# car.net
KiCad netlist of a schematic drawn in EAGLE
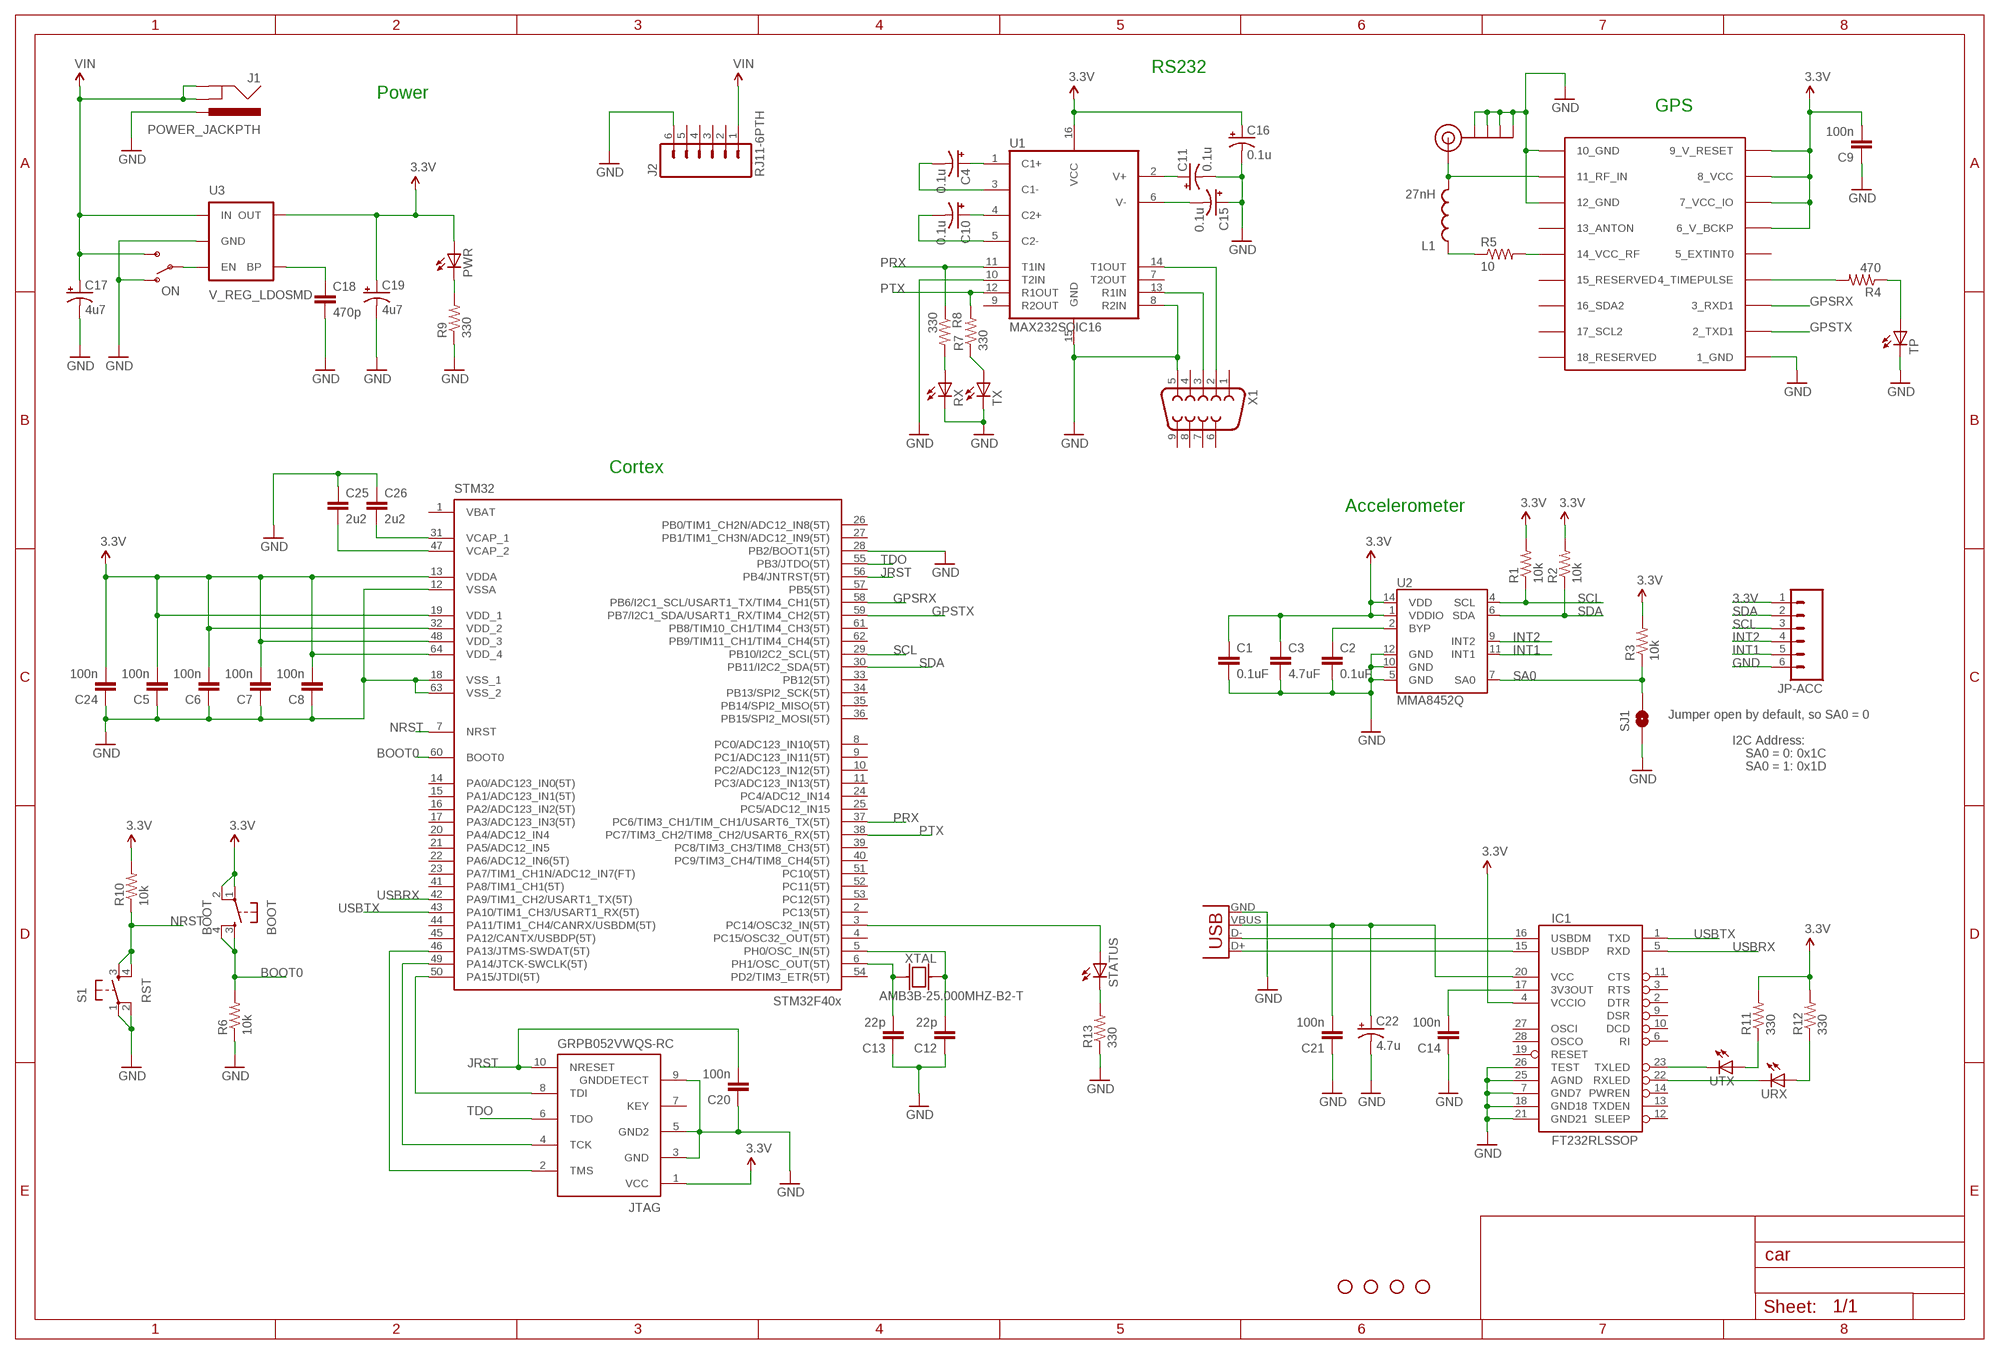
[diagram p0: schematic, sheet 1]

(export (version "E")
  (design (tool "Eeschema 10.0.6"))
  (components
    (comp (ref "BOOT")
      (value "BOOT")
      (footprint "eagle-import:TACTILE_SWITCH_SMD")
      (libsource (lib "eagle-import") (part "TAC_SWITCHSMD"))
    )
    (comp (ref "C1")
      (value "0.1uF")
      (footprint "eagle-import:0603-CAP")
      (libsource (lib "eagle-import") (part "CAP0603-CAP"))
    )
    (comp (ref "C2")
      (value "0.1uF")
      (footprint "eagle-import:0603-CAP")
      (libsource (lib "eagle-import") (part "CAP0603-CAP"))
    )
    (comp (ref "C3")
      (value "4.7uF")
      (footprint "eagle-import:0603-CAP")
      (libsource (lib "eagle-import") (part "CAP0603-CAP"))
    )
    (comp (ref "C4")
      (value "0.1u")
      (footprint "eagle-import:EIA3216")
      (libsource (lib "eagle-import") (part "CAP_POL1206"))
    )
    (comp (ref "C5")
      (value "100n")
      (footprint "eagle-import:0603-CAP")
      (libsource (lib "eagle-import") (part "SparkFun-Passives_CAP0603-CAP"))
    )
    (comp (ref "C6")
      (value "100n")
      (footprint "eagle-import:0603-CAP")
      (libsource (lib "eagle-import") (part "SparkFun-Passives_CAP0603-CAP"))
    )
    (comp (ref "C7")
      (value "100n")
      (footprint "eagle-import:0603-CAP")
      (libsource (lib "eagle-import") (part "SparkFun-Passives_CAP0603-CAP"))
    )
    (comp (ref "C8")
      (value "100n")
      (footprint "eagle-import:0603-CAP")
      (libsource (lib "eagle-import") (part "SparkFun-Passives_CAP0603-CAP"))
    )
    (comp (ref "C9")
      (value "100n")
      (footprint "eagle-import:0603-CAP")
      (libsource (lib "eagle-import") (part "SparkFun-Passives_CAP0603-CAP"))
    )
    (comp (ref "C10")
      (value "0.1u")
      (footprint "eagle-import:EIA3216")
      (libsource (lib "eagle-import") (part "CAP_POL1206"))
    )
    (comp (ref "C11")
      (value "0.1u")
      (footprint "eagle-import:EIA3216")
      (libsource (lib "eagle-import") (part "CAP_POL1206"))
    )
    (comp (ref "C12")
      (value "22p")
      (footprint "eagle-import:0603-CAP")
      (libsource (lib "eagle-import") (part "SparkFun-Passives_CAP0603-CAP"))
    )
    (comp (ref "C13")
      (value "22p")
      (footprint "eagle-import:0603-CAP")
      (libsource (lib "eagle-import") (part "SparkFun-Passives_CAP0603-CAP"))
    )
    (comp (ref "C14")
      (value "100n")
      (footprint "eagle-import:0603-CAP")
      (libsource (lib "eagle-import") (part "SparkFun-Passives_CAP0603-CAP"))
    )
    (comp (ref "C15")
      (value "0.1u")
      (footprint "eagle-import:EIA3216")
      (libsource (lib "eagle-import") (part "CAP_POL1206"))
    )
    (comp (ref "C16")
      (value "0.1u")
      (footprint "eagle-import:EIA3216")
      (libsource (lib "eagle-import") (part "CAP_POL1206"))
    )
    (comp (ref "C17")
      (value "4u7")
      (footprint "eagle-import:EIA3216")
      (libsource (lib "eagle-import") (part "CAP_POL1206"))
    )
    (comp (ref "C18")
      (value "470p")
      (footprint "eagle-import:0603-CAP")
      (libsource (lib "eagle-import") (part "SparkFun-Passives_CAP0603-CAP"))
    )
    (comp (ref "C19")
      (value "4u7")
      (footprint "eagle-import:EIA3216")
      (libsource (lib "eagle-import") (part "CAP_POL1206"))
    )
    (comp (ref "C20")
      (value "100n")
      (footprint "eagle-import:0603-CAP")
      (libsource (lib "eagle-import") (part "SparkFun-Passives_CAP0603-CAP"))
    )
    (comp (ref "C21")
      (value "100n")
      (footprint "eagle-import:0603-CAP")
      (libsource (lib "eagle-import") (part "SparkFun-Passives_CAP0603-CAP"))
    )
    (comp (ref "C22")
      (value "4.7u")
      (footprint "eagle-import:EIA3216")
      (libsource (lib "eagle-import") (part "CAP_POL1206"))
    )
    (comp (ref "C24")
      (value "100n")
      (footprint "eagle-import:0603-CAP")
      (libsource (lib "eagle-import") (part "SparkFun-Passives_CAP0603-CAP"))
    )
    (comp (ref "C25")
      (value "2u2")
      (footprint "eagle-import:0603-CAP")
      (libsource (lib "eagle-import") (part "SparkFun-Passives_CAP0603-CAP"))
    )
    (comp (ref "C26")
      (value "2u2")
      (footprint "eagle-import:0603-CAP")
      (libsource (lib "eagle-import") (part "SparkFun-Passives_CAP0603-CAP"))
    )
    (comp (ref "IC1")
      (value "FT232RLSSOP")
      (footprint "eagle-import:SSOP28DB")
      (libsource (lib "eagle-import") (part "FT232RLSSOP"))
    )
    (comp (ref "J$1")
      (value "SMA_EDGE")
      (footprint "eagle-import:SMA-EDGE")
      (libsource (lib "eagle-import") (part "SMA_EDGE"))
    )
    (comp (ref "J1")
      (value "POWER_JACKPTH")
      (footprint "eagle-import:POWER_JACK_PTH")
      (libsource (lib "eagle-import") (part "POWER_JACKPTH"))
    )
    (comp (ref "J2")
      (value "RJ11-6PTH")
      (footprint "eagle-import:RJ11-6")
      (libsource (lib "eagle-import") (part "RJ11-6PTH"))
    )
    (comp (ref "JP-ACC")
      (value "M06SIP")
      (footprint "eagle-import:1X06")
      (libsource (lib "eagle-import") (part "M06SIP"))
    )
    (comp (ref "JP1")
      (value "STAND-OFF")
      (footprint "eagle-import:STAND-OFF")
      (libsource (lib "eagle-import") (part "STAND-OFF"))
    )
    (comp (ref "JP2")
      (value "STAND-OFF")
      (footprint "eagle-import:STAND-OFF")
      (libsource (lib "eagle-import") (part "STAND-OFF"))
    )
    (comp (ref "JP3")
      (value "STAND-OFF")
      (footprint "eagle-import:STAND-OFF")
      (libsource (lib "eagle-import") (part "STAND-OFF"))
    )
    (comp (ref "JP4")
      (value "STAND-OFF")
      (footprint "eagle-import:STAND-OFF")
      (libsource (lib "eagle-import") (part "STAND-OFF"))
    )
    (comp (ref "JTAG")
      (value "GRPB052VWQS-RC")
      (footprint "eagle-import:DEBUG")
      (libsource (lib "eagle-import") (part "GRPB052VWQS-RC"))
    )
    (comp (ref "L1")
      (value "27nH")
      (footprint "eagle-import:0603")
      (libsource (lib "eagle-import") (part "INDUCTOR0603"))
    )
    (comp (ref "ON")
      (value "SWITCH-SPDTPTH")
      (footprint "eagle-import:SWITCH-SPDT")
      (libsource (lib "eagle-import") (part "SWITCH-SPDTPTH"))
    )
    (comp (ref "PWR")
      (value "LED0603")
      (footprint "eagle-import:LED-0603")
      (libsource (lib "eagle-import") (part "LED0603"))
    )
    (comp (ref "R1")
      (value "10k")
      (footprint "eagle-import:0603-RES")
      (libsource (lib "eagle-import") (part "RESISTOR0603-RES"))
    )
    (comp (ref "R2")
      (value "10k")
      (footprint "eagle-import:0603-RES")
      (libsource (lib "eagle-import") (part "RESISTOR0603-RES"))
    )
    (comp (ref "R3")
      (value "10k")
      (footprint "eagle-import:0603-RES")
      (libsource (lib "eagle-import") (part "RESISTOR0603-RES"))
    )
    (comp (ref "R4")
      (value "470")
      (footprint "eagle-import:0603-RES")
      (libsource (lib "eagle-import") (part "SparkFun-Passives_RESISTOR0603-RES"))
    )
    (comp (ref "R5")
      (value "10")
      (footprint "eagle-import:0603-RES")
      (libsource (lib "eagle-import") (part "SparkFun-Passives_RESISTOR0603-RES"))
    )
    (comp (ref "R6")
      (value "10k")
      (footprint "eagle-import:0603-RES")
      (libsource (lib "eagle-import") (part "SparkFun-Passives_RESISTOR0603-RES"))
    )
    (comp (ref "R7")
      (value "330")
      (footprint "eagle-import:0603-RES")
      (libsource (lib "eagle-import") (part "SparkFun-Passives_RESISTOR0603-RES"))
    )
    (comp (ref "R8")
      (value "330")
      (footprint "eagle-import:0603-RES")
      (libsource (lib "eagle-import") (part "SparkFun-Passives_RESISTOR0603-RES"))
    )
    (comp (ref "R9")
      (value "330")
      (footprint "eagle-import:0603-RES")
      (libsource (lib "eagle-import") (part "SparkFun-Passives_RESISTOR0603-RES"))
    )
    (comp (ref "R10")
      (value "10k")
      (footprint "eagle-import:0603-RES")
      (libsource (lib "eagle-import") (part "SparkFun-Passives_RESISTOR0603-RES"))
    )
    (comp (ref "R11")
      (value "330")
      (footprint "eagle-import:0603-RES")
      (libsource (lib "eagle-import") (part "RESISTOR0603-RES"))
    )
    (comp (ref "R12")
      (value "330")
      (footprint "eagle-import:0603-RES")
      (libsource (lib "eagle-import") (part "RESISTOR0603-RES"))
    )
    (comp (ref "R13")
      (value "330")
      (footprint "eagle-import:0603-RES")
      (libsource (lib "eagle-import") (part "SparkFun-Passives_RESISTOR0603-RES"))
    )
    (comp (ref "RX")
      (value "LED0603")
      (footprint "eagle-import:LED-0603")
      (libsource (lib "eagle-import") (part "LED0603"))
    )
    (comp (ref "S1")
      (value "RST")
      (footprint "eagle-import:TACTILE_SWITCH_SMD")
      (libsource (lib "eagle-import") (part "TAC_SWITCHSMD"))
    )
    (comp (ref "SJ1")
      (value "SOLDERJUMPERNO")
      (footprint "eagle-import:SJ_2S-NO")
      (libsource (lib "eagle-import") (part "SOLDERJUMPERNO"))
    )
    (comp (ref "STATUS")
      (value "LED0603")
      (footprint "eagle-import:LED-0603")
      (libsource (lib "eagle-import") (part "LED0603"))
    )
    (comp (ref "STM32")
      (value "STM32F405R")
      (footprint "eagle-import:TQFP64")
      (libsource (lib "eagle-import") (part "STM32F405R"))
    )
    (comp (ref "TP")
      (value "LED0603")
      (footprint "eagle-import:LED-0603")
      (libsource (lib "eagle-import") (part "LED0603"))
    )
    (comp (ref "TX")
      (value "LED0603")
      (footprint "eagle-import:LED-0603")
      (libsource (lib "eagle-import") (part "LED0603"))
    )
    (comp (ref "U$1")
      (value "UBLOX_MAX-6")
      (footprint "eagle-import:UBLOX_MAX-6")
      (libsource (lib "eagle-import") (part "UBLOX_MAX-6"))
    )
    (comp (ref "U1")
      (value "MAX232SOIC16")
      (footprint "eagle-import:SO016")
      (libsource (lib "eagle-import") (part "MAX232SOIC16"))
    )
    (comp (ref "U2")
      (value "MMA8452Q")
      (footprint "eagle-import:QFN-16_0.5MM")
      (libsource (lib "eagle-import") (part "MMA8452Q"))
    )
    (comp (ref "U3")
      (value "V_REG_LDOSMD")
      (footprint "eagle-import:SOT23-5")
      (libsource (lib "eagle-import") (part "V_REG_LDOSMD"))
    )
    (comp (ref "URX")
      (value "LED0603")
      (footprint "eagle-import:LED-0603")
      (libsource (lib "eagle-import") (part "LED0603"))
    )
    (comp (ref "USB")
      (value "USB-SMD-NS")
      (footprint "eagle-import:USB-MINIB-NOSTOP")
      (libsource (lib "eagle-import") (part "USB-SMD-NS"))
    )
    (comp (ref "UTX")
      (value "LED0603")
      (footprint "eagle-import:LED-0603")
      (libsource (lib "eagle-import") (part "LED0603"))
    )
    (comp (ref "X1")
      (value "DB9FEMALE")
      (footprint "eagle-import:DB9")
      (libsource (lib "eagle-import") (part "DB9FEMALE"))
    )
    (comp (ref "XTAL")
      (value "AMB3B-25.000MHZ-B2-T")
      (footprint "eagle-import:4LCC")
      (libsource (lib "eagle-import") (part "AMB3B-25.000MHZ-B2-T"))
    )
  )
  (nets
    (net (code "1") (name "/BOOT0") (class "Default")
      (node (ref "BOOT") (pin "3") (pinfunction "3_3") (pintype "passive"))
      (node (ref "BOOT") (pin "4") (pinfunction "4_4") (pintype "passive"))
      (node (ref "R6") (pin "2") (pinfunction "2_2") (pintype "passive"))
      (node (ref "STM32") (pin "60") (pinfunction "BOOT0_60") (pintype "bidirectional"))
    )
    (net (code "2") (name "/GPSRX") (class "Default")
      (node (ref "STM32") (pin "58") (pinfunction "PB6/I2C1_SCL/USART1_TX/TIM4_CH1(5T)_58") (pintype "bidirectional"))
      (node (ref "U$1") (pin "3_RXD1") (pinfunction "3_RXD1_3_RXD1") (pintype "bidirectional"))
    )
    (net (code "3") (name "/GPSTX") (class "Default")
      (node (ref "STM32") (pin "59") (pinfunction "PB7/I2C1_SDA/USART1_RX/TIM4_CH2(5T)_59") (pintype "bidirectional"))
      (node (ref "U$1") (pin "2_TXD1") (pinfunction "2_TXD1_2_TXD1") (pintype "bidirectional"))
    )
    (net (code "4") (name "/INT1") (class "Default")
      (node (ref "JP-ACC") (pin "5") (pinfunction "5_5") (pintype "passive"))
      (node (ref "U2") (pin "11") (pinfunction "INT1_11") (pintype "bidirectional"))
    )
    (net (code "5") (name "/INT2") (class "Default")
      (node (ref "JP-ACC") (pin "4") (pinfunction "4_4") (pintype "passive"))
      (node (ref "U2") (pin "9") (pinfunction "INT2_9") (pintype "bidirectional"))
    )
    (net (code "6") (name "/JRST") (class "Default")
      (node (ref "C20") (pin "2") (pinfunction "2_2") (pintype "passive"))
      (node (ref "JTAG") (pin "10") (pinfunction "NRESET_10") (pintype "bidirectional"))
      (node (ref "STM32") (pin "56") (pinfunction "PB4/JNTRST(5T)_56") (pintype "bidirectional"))
    )
    (net (code "7") (name "/NRST") (class "Default")
      (node (ref "R10") (pin "1") (pinfunction "1_1") (pintype "passive"))
      (node (ref "S1") (pin "3") (pinfunction "3_3") (pintype "passive"))
      (node (ref "S1") (pin "4") (pinfunction "4_4") (pintype "passive"))
      (node (ref "STM32") (pin "7") (pinfunction "NRST_7") (pintype "bidirectional"))
    )
    (net (code "8") (name "/PRX") (class "Default")
      (node (ref "R8") (pin "1") (pinfunction "1_1") (pintype "passive"))
      (node (ref "STM32") (pin "37") (pinfunction "PC6/TIM3_CH1/TIM_CH1/USART6_TX(5T)_37") (pintype "bidirectional"))
      (node (ref "U1") (pin "11") (pinfunction "T1IN_11") (pintype "input"))
    )
    (net (code "9") (name "/PTX") (class "Default")
      (node (ref "R7") (pin "2") (pinfunction "2_2") (pintype "passive"))
      (node (ref "STM32") (pin "38") (pinfunction "PC7/TIM3_CH2/TIM8_CH2/USART6_RX(5T)_38") (pintype "bidirectional"))
      (node (ref "U1") (pin "12") (pinfunction "R1OUT_12") (pintype "output"))
    )
    (net (code "10") (name "/SA0") (class "Default")
      (node (ref "R3") (pin "1") (pinfunction "1_1") (pintype "passive"))
      (node (ref "SJ1") (pin "2") (pinfunction "2_2") (pintype "passive"))
      (node (ref "U2") (pin "7") (pinfunction "SA0_7") (pintype "bidirectional"))
    )
    (net (code "11") (name "/SCL") (class "Default")
      (node (ref "JP-ACC") (pin "3") (pinfunction "3_3") (pintype "passive"))
      (node (ref "R1") (pin "1") (pinfunction "1_1") (pintype "passive"))
      (node (ref "STM32") (pin "29") (pinfunction "PB10/I2C2_SCL(5T)_29") (pintype "bidirectional"))
      (node (ref "U2") (pin "4") (pinfunction "SCL_4") (pintype "bidirectional"))
    )
    (net (code "12") (name "/SDA") (class "Default")
      (node (ref "JP-ACC") (pin "2") (pinfunction "2_2") (pintype "passive"))
      (node (ref "R2") (pin "1") (pinfunction "1_1") (pintype "passive"))
      (node (ref "STM32") (pin "30") (pinfunction "PB11/I2C2_SDA(5T)_30") (pintype "bidirectional"))
      (node (ref "U2") (pin "6") (pinfunction "SDA_6") (pintype "bidirectional"))
    )
    (net (code "13") (name "/TDO") (class "Default")
      (node (ref "JTAG") (pin "6") (pinfunction "TDO_6") (pintype "bidirectional"))
      (node (ref "STM32") (pin "55") (pinfunction "PB3/JTDO(5T)_55") (pintype "bidirectional"))
    )
    (net (code "14") (name "/USBRX") (class "Default")
      (node (ref "IC1") (pin "5") (pinfunction "RXD_5") (pintype "input"))
      (node (ref "STM32") (pin "42") (pinfunction "PA9/TIM1_CH2/USART1_TX(5T)_42") (pintype "bidirectional"))
    )
    (net (code "15") (name "/USBTX") (class "Default")
      (node (ref "IC1") (pin "1") (pinfunction "TXD_1") (pintype "output"))
      (node (ref "STM32") (pin "43") (pinfunction "PA10/TIM1_CH3/USART1_RX(5T)_43") (pintype "bidirectional"))
    )
    (net (code "16") (name "3.3V") (class "Default")
      (node (ref "BOOT") (pin "1") (pinfunction "1_1") (pintype "passive"))
      (node (ref "BOOT") (pin "2") (pinfunction "2_2") (pintype "passive"))
      (node (ref "C1") (pin "1") (pinfunction "1_1") (pintype "passive"))
      (node (ref "C16") (pin "A") (pinfunction "+_A") (pintype "passive"))
      (node (ref "C19") (pin "A") (pinfunction "+_A") (pintype "passive"))
      (node (ref "C24") (pin "2") (pinfunction "2_2") (pintype "passive"))
      (node (ref "C3") (pin "1") (pinfunction "1_1") (pintype "passive"))
      (node (ref "C5") (pin "2") (pinfunction "2_2") (pintype "passive"))
      (node (ref "C6") (pin "2") (pinfunction "2_2") (pintype "passive"))
      (node (ref "C7") (pin "2") (pinfunction "2_2") (pintype "passive"))
      (node (ref "C8") (pin "2") (pinfunction "2_2") (pintype "passive"))
      (node (ref "C9") (pin "2") (pinfunction "2_2") (pintype "passive"))
      (node (ref "IC1") (pin "4") (pinfunction "VCCIO_4") (pintype "power_in"))
      (node (ref "JP-ACC") (pin "1") (pinfunction "1_1") (pintype "passive"))
      (node (ref "JTAG") (pin "1") (pinfunction "VCC_1") (pintype "bidirectional"))
      (node (ref "PWR") (pin "A") (pinfunction "A_A") (pintype "passive"))
      (node (ref "R1") (pin "2") (pinfunction "2_2") (pintype "passive"))
      (node (ref "R10") (pin "2") (pinfunction "2_2") (pintype "passive"))
      (node (ref "R11") (pin "2") (pinfunction "2_2") (pintype "passive"))
      (node (ref "R12") (pin "2") (pinfunction "2_2") (pintype "passive"))
      (node (ref "R2") (pin "2") (pinfunction "2_2") (pintype "passive"))
      (node (ref "R3") (pin "2") (pinfunction "2_2") (pintype "passive"))
      (node (ref "STM32") (pin "13") (pinfunction "VDDA_13") (pintype "bidirectional"))
      (node (ref "STM32") (pin "19") (pinfunction "VDD_1_19") (pintype "bidirectional"))
      (node (ref "STM32") (pin "32") (pinfunction "VDD_2_32") (pintype "bidirectional"))
      (node (ref "STM32") (pin "48") (pinfunction "VDD_3_48") (pintype "bidirectional"))
      (node (ref "STM32") (pin "64") (pinfunction "VDD_4_64") (pintype "bidirectional"))
      (node (ref "U$1") (pin "6_V_BCKP") (pinfunction "6_V_BCKP_6_V_BCKP") (pintype "bidirectional"))
      (node (ref "U$1") (pin "7_VCC_IO") (pinfunction "7_VCC_IO_7_VCC_IO") (pintype "power_in"))
      (node (ref "U$1") (pin "8_VCC") (pinfunction "8_VCC_8_VCC") (pintype "power_in"))
      (node (ref "U$1") (pin "9_V_RESET") (pinfunction "9_V_RESET_9_V_RESET") (pintype "power_in"))
      (node (ref "U1") (pin "16") (pinfunction "VCC_16") (pintype "bidirectional"))
      (node (ref "U2") (pin "1") (pinfunction "VDDIO_1") (pintype "bidirectional"))
      (node (ref "U2") (pin "14") (pinfunction "VDD_14") (pintype "bidirectional"))
      (node (ref "U3") (pin "5") (pinfunction "OUT_5") (pintype "passive"))
    )
    (net (code "17") (name "GND") (class "Default")
      (node (ref "C1") (pin "2") (pinfunction "2_2") (pintype "passive"))
      (node (ref "C11") (pin "C") (pinfunction "-_C") (pintype "passive"))
      (node (ref "C12") (pin "1") (pinfunction "1_1") (pintype "passive"))
      (node (ref "C13") (pin "1") (pinfunction "1_1") (pintype "passive"))
      (node (ref "C14") (pin "1") (pinfunction "1_1") (pintype "passive"))
      (node (ref "C15") (pin "A") (pinfunction "+_A") (pintype "passive"))
      (node (ref "C16") (pin "C") (pinfunction "-_C") (pintype "passive"))
      (node (ref "C17") (pin "C") (pinfunction "-_C") (pintype "passive"))
      (node (ref "C18") (pin "2") (pinfunction "2_2") (pintype "passive"))
      (node (ref "C19") (pin "C") (pinfunction "-_C") (pintype "passive"))
      (node (ref "C2") (pin "2") (pinfunction "2_2") (pintype "passive"))
      (node (ref "C20") (pin "1") (pinfunction "1_1") (pintype "passive"))
      (node (ref "C21") (pin "1") (pinfunction "1_1") (pintype "passive"))
      (node (ref "C22") (pin "C") (pinfunction "-_C") (pintype "passive"))
      (node (ref "C24") (pin "1") (pinfunction "1_1") (pintype "passive"))
      (node (ref "C25") (pin "1") (pinfunction "1_1") (pintype "passive"))
      (node (ref "C26") (pin "1") (pinfunction "1_1") (pintype "passive"))
      (node (ref "C3") (pin "2") (pinfunction "2_2") (pintype "passive"))
      (node (ref "C5") (pin "1") (pinfunction "1_1") (pintype "passive"))
      (node (ref "C6") (pin "1") (pinfunction "1_1") (pintype "passive"))
      (node (ref "C7") (pin "1") (pinfunction "1_1") (pintype "passive"))
      (node (ref "C8") (pin "1") (pinfunction "1_1") (pintype "passive"))
      (node (ref "C9") (pin "1") (pinfunction "1_1") (pintype "passive"))
      (node (ref "IC1") (pin "18") (pinfunction "GND18_18") (pintype "power_in"))
      (node (ref "IC1") (pin "21") (pinfunction "GND21_21") (pintype "power_in"))
      (node (ref "IC1") (pin "25") (pinfunction "AGND_25") (pintype "power_in"))
      (node (ref "IC1") (pin "26") (pinfunction "TEST_26") (pintype "input"))
      (node (ref "IC1") (pin "7") (pinfunction "GND7_7") (pintype "power_in"))
      (node (ref "J$1") (pin "GND@0") (pinfunction "GND_GND@0") (pintype "bidirectional"))
      (node (ref "J$1") (pin "GND@1") (pinfunction "GND_GND@1") (pintype "bidirectional"))
      (node (ref "J$1") (pin "GND@2") (pinfunction "GND_GND@2") (pintype "bidirectional"))
      (node (ref "J$1") (pin "GND@3") (pinfunction "GND_GND@3") (pintype "bidirectional"))
      (node (ref "J1") (pin "PWR") (pinfunction "PWR_PWR") (pintype "bidirectional"))
      (node (ref "J2") (pin "6") (pinfunction "6_6") (pintype "passive"))
      (node (ref "JP-ACC") (pin "6") (pinfunction "6_6") (pintype "passive"))
      (node (ref "JTAG") (pin "3") (pinfunction "GND_3") (pintype "bidirectional"))
      (node (ref "JTAG") (pin "5") (pinfunction "GND2_5") (pintype "bidirectional"))
      (node (ref "JTAG") (pin "9") (pinfunction "GNDDETECT_9") (pintype "bidirectional"))
      (node (ref "ON") (pin "1") (pinfunction "O_1") (pintype "passive"))
      (node (ref "R13") (pin "1") (pinfunction "1_1") (pintype "passive"))
      (node (ref "R6") (pin "1") (pinfunction "1_1") (pintype "passive"))
      (node (ref "R9") (pin "1") (pinfunction "1_1") (pintype "passive"))
      (node (ref "RX") (pin "C") (pinfunction "C_C") (pintype "passive"))
      (node (ref "S1") (pin "1") (pinfunction "1_1") (pintype "passive"))
      (node (ref "S1") (pin "2") (pinfunction "2_2") (pintype "passive"))
      (node (ref "SJ1") (pin "1") (pinfunction "1_1") (pintype "passive"))
      (node (ref "STM32") (pin "12") (pinfunction "VSSA_12") (pintype "bidirectional"))
      (node (ref "STM32") (pin "18") (pinfunction "VSS_1_18") (pintype "bidirectional"))
      (node (ref "STM32") (pin "28") (pinfunction "PB2/BOOT1(5T)_28") (pintype "bidirectional"))
      (node (ref "STM32") (pin "63") (pinfunction "VSS_2_63") (pintype "bidirectional"))
      (node (ref "TP") (pin "C") (pinfunction "C_C") (pintype "passive"))
      (node (ref "TX") (pin "C") (pinfunction "C_C") (pintype "passive"))
      (node (ref "U$1") (pin "10_GND") (pinfunction "10_GND_10_GND") (pintype "power_in"))
      (node (ref "U$1") (pin "12_GND") (pinfunction "12_GND_12_GND") (pintype "power_in"))
      (node (ref "U$1") (pin "1_GND") (pinfunction "1_GND_1_GND") (pintype "power_in"))
      (node (ref "U1") (pin "10") (pinfunction "T2IN_10") (pintype "input"))
      (node (ref "U1") (pin "15") (pinfunction "GND_15") (pintype "bidirectional"))
      (node (ref "U1") (pin "8") (pinfunction "R2IN_8") (pintype "input"))
      (node (ref "U2") (pin "10") (pinfunction "GND_10") (pintype "bidirectional"))
      (node (ref "U2") (pin "12") (pinfunction "GND_12") (pintype "bidirectional"))
      (node (ref "U2") (pin "5") (pinfunction "GND_5") (pintype "bidirectional"))
      (node (ref "U3") (pin "2") (pinfunction "GND_2") (pintype "input"))
      (node (ref "USB") (pin "GND") (pinfunction "GND_GND") (pintype "bidirectional"))
      (node (ref "X1") (pin "5") (pinfunction "5_5") (pintype "passive"))
    )
    (net (code "18") (name "Net-(C4-+)") (class "Default")
      (node (ref "C4") (pin "A") (pinfunction "+_A") (pintype "passive"))
      (node (ref "U1") (pin "1") (pinfunction "C1+_1") (pintype "bidirectional"))
    )
    (net (code "19") (name "Net-(C4--)") (class "Default")
      (node (ref "C4") (pin "C") (pinfunction "-_C") (pintype "passive"))
      (node (ref "U1") (pin "3") (pinfunction "C1-_3") (pintype "bidirectional"))
    )
    (net (code "20") (name "Net-(C10-+)") (class "Default")
      (node (ref "C10") (pin "A") (pinfunction "+_A") (pintype "passive"))
      (node (ref "U1") (pin "4") (pinfunction "C2+_4") (pintype "bidirectional"))
    )
    (net (code "21") (name "Net-(C10--)") (class "Default")
      (node (ref "C10") (pin "C") (pinfunction "-_C") (pintype "passive"))
      (node (ref "U1") (pin "5") (pinfunction "C2-_5") (pintype "bidirectional"))
    )
    (net (code "22") (name "Net-(C11-+)") (class "Default")
      (node (ref "C11") (pin "A") (pinfunction "+_A") (pintype "passive"))
      (node (ref "U1") (pin "2") (pinfunction "V+_2") (pintype "bidirectional"))
    )
    (net (code "23") (name "Net-(C15--)") (class "Default")
      (node (ref "C15") (pin "C") (pinfunction "-_C") (pintype "passive"))
      (node (ref "U1") (pin "6") (pinfunction "V-_6") (pintype "bidirectional"))
    )
    (net (code "24") (name "Net-(C22-+)") (class "Default")
      (node (ref "C21") (pin "2") (pinfunction "2_2") (pintype "passive"))
      (node (ref "C22") (pin "A") (pinfunction "+_A") (pintype "passive"))
      (node (ref "IC1") (pin "20") (pinfunction "VCC_20") (pintype "power_in"))
      (node (ref "USB") (pin "VBUS") (pinfunction "VBUS_VBUS") (pintype "bidirectional"))
    )
    (net (code "25") (name "Net-(IC1-3V3OUT)") (class "Default")
      (node (ref "C14") (pin "2") (pinfunction "2_2") (pintype "passive"))
      (node (ref "IC1") (pin "17") (pinfunction "3V3OUT_17") (pintype "output"))
    )
    (net (code "26") (name "Net-(IC1-RXLED)") (class "Default")
      (node (ref "IC1") (pin "22") (pinfunction "RXLED_22") (pintype "input"))
      (node (ref "URX") (pin "C") (pinfunction "C_C") (pintype "passive"))
    )
    (net (code "27") (name "Net-(IC1-TXLED)") (class "Default")
      (node (ref "IC1") (pin "23") (pinfunction "TXLED_23") (pintype "input"))
      (node (ref "UTX") (pin "C") (pinfunction "C_C") (pintype "passive"))
    )
    (net (code "28") (name "Net-(IC1-USBDM)") (class "Default")
      (node (ref "IC1") (pin "16") (pinfunction "USBDM_16") (pintype "bidirectional"))
      (node (ref "USB") (pin "D-") (pinfunction "D-_D-") (pintype "bidirectional"))
    )
    (net (code "29") (name "Net-(IC1-USBDP)") (class "Default")
      (node (ref "IC1") (pin "15") (pinfunction "USBDP_15") (pintype "bidirectional"))
      (node (ref "USB") (pin "D+") (pinfunction "D+_D+") (pintype "bidirectional"))
    )
    (net (code "30") (name "Net-(J$1-SIGNAL)") (class "Default")
      (node (ref "J$1") (pin "SIG") (pinfunction "SIGNAL_SIG") (pintype "bidirectional"))
      (node (ref "L1") (pin "2") (pinfunction "2_2") (pintype "passive"))
      (node (ref "U$1") (pin "11_RF_IN") (pinfunction "11_RF_IN_11_RF_IN") (pintype "bidirectional"))
    )
    (net (code "31") (name "Net-(JTAG-TCK)") (class "Default")
      (node (ref "JTAG") (pin "4") (pinfunction "TCK_4") (pintype "bidirectional"))
      (node (ref "STM32") (pin "49") (pinfunction "PA14/JTCK-SWCLK(5T)_49") (pintype "bidirectional"))
    )
    (net (code "32") (name "Net-(JTAG-TDI)") (class "Default")
      (node (ref "JTAG") (pin "8") (pinfunction "TDI_8") (pintype "bidirectional"))
      (node (ref "STM32") (pin "50") (pinfunction "PA15/JTDI(5T)_50") (pintype "bidirectional"))
    )
    (net (code "33") (name "Net-(JTAG-TMS)") (class "Default")
      (node (ref "JTAG") (pin "2") (pinfunction "TMS_2") (pintype "bidirectional"))
      (node (ref "STM32") (pin "46") (pinfunction "PA13/JTMS-SWDAT(5T)_46") (pintype "bidirectional"))
    )
    (net (code "34") (name "Net-(L1-Pad1)") (class "Default")
      (node (ref "L1") (pin "1") (pinfunction "1_1") (pintype "passive"))
      (node (ref "R5") (pin "1") (pinfunction "1_1") (pintype "passive"))
    )
    (net (code "35") (name "Net-(ON-P)") (class "Default")
      (node (ref "ON") (pin "2") (pinfunction "P_2") (pintype "passive"))
      (node (ref "U3") (pin "3") (pinfunction "EN_3") (pintype "input"))
    )
    (net (code "36") (name "Net-(PWR-PadC)") (class "Default")
      (node (ref "PWR") (pin "C") (pinfunction "C_C") (pintype "passive"))
      (node (ref "R9") (pin "2") (pinfunction "2_2") (pintype "passive"))
    )
    (net (code "37") (name "Net-(R4-Pad1)") (class "Default")
      (node (ref "R4") (pin "1") (pinfunction "1_1") (pintype "passive"))
      (node (ref "TP") (pin "A") (pinfunction "A_A") (pintype "passive"))
    )
    (net (code "38") (name "Net-(R4-Pad2)") (class "Default")
      (node (ref "R4") (pin "2") (pinfunction "2_2") (pintype "passive"))
      (node (ref "U$1") (pin "4_TIMEPULSE") (pinfunction "4_TIMEPULSE_4_TIMEPULSE") (pintype "bidirectional"))
    )
    (net (code "39") (name "Net-(R5-Pad2)") (class "Default")
      (node (ref "R5") (pin "2") (pinfunction "2_2") (pintype "passive"))
      (node (ref "U$1") (pin "14_VCC_RF") (pinfunction "14_VCC_RF_14_VCC_RF") (pintype "bidirectional"))
    )
    (net (code "40") (name "Net-(R7-Pad1)") (class "Default")
      (node (ref "R7") (pin "1") (pinfunction "1_1") (pintype "passive"))
      (node (ref "TX") (pin "A") (pinfunction "A_A") (pintype "passive"))
    )
    (net (code "41") (name "Net-(R8-Pad2)") (class "Default")
      (node (ref "R8") (pin "2") (pinfunction "2_2") (pintype "passive"))
      (node (ref "RX") (pin "A") (pinfunction "A_A") (pintype "passive"))
    )
    (net (code "42") (name "Net-(R11-Pad1)") (class "Default")
      (node (ref "R11") (pin "1") (pinfunction "1_1") (pintype "passive"))
      (node (ref "UTX") (pin "A") (pinfunction "A_A") (pintype "passive"))
    )
    (net (code "43") (name "Net-(R12-Pad1)") (class "Default")
      (node (ref "R12") (pin "1") (pinfunction "1_1") (pintype "passive"))
      (node (ref "URX") (pin "A") (pinfunction "A_A") (pintype "passive"))
    )
    (net (code "44") (name "Net-(R13-Pad2)") (class "Default")
      (node (ref "R13") (pin "2") (pinfunction "2_2") (pintype "passive"))
      (node (ref "STATUS") (pin "C") (pinfunction "C_C") (pintype "passive"))
    )
    (net (code "45") (name "Net-(STM32-PC14{slash}OSC32_IN(5T))") (class "Default")
      (node (ref "STATUS") (pin "A") (pinfunction "A_A") (pintype "passive"))
      (node (ref "STM32") (pin "3") (pinfunction "PC14/OSC32_IN(5T)_3") (pintype "bidirectional"))
    )
    (net (code "46") (name "Net-(STM32-PH0{slash}OSC_IN(5T))") (class "Default")
      (node (ref "C12") (pin "2") (pinfunction "2_2") (pintype "passive"))
      (node (ref "STM32") (pin "5") (pinfunction "PH0/OSC_IN(5T)_5") (pintype "bidirectional"))
      (node (ref "XTAL") (pin "3") (pinfunction "P$2_3") (pintype "bidirectional"))
    )
    (net (code "47") (name "Net-(STM32-PH1{slash}OSC_OUT(5T))") (class "Default")
      (node (ref "C13") (pin "2") (pinfunction "2_2") (pintype "passive"))
      (node (ref "STM32") (pin "6") (pinfunction "PH1/OSC_OUT(5T)_6") (pintype "bidirectional"))
      (node (ref "XTAL") (pin "1") (pinfunction "P$1_1") (pintype "bidirectional"))
    )
    (net (code "48") (name "Net-(STM32-VCAP_1)") (class "Default")
      (node (ref "C26") (pin "2") (pinfunction "2_2") (pintype "passive"))
      (node (ref "STM32") (pin "31") (pinfunction "VCAP_1_31") (pintype "bidirectional"))
    )
    (net (code "49") (name "Net-(STM32-VCAP_2)") (class "Default")
      (node (ref "C25") (pin "2") (pinfunction "2_2") (pintype "passive"))
      (node (ref "STM32") (pin "47") (pinfunction "VCAP_2_47") (pintype "bidirectional"))
    )
    (net (code "50") (name "Net-(U1-R1IN)") (class "Default")
      (node (ref "U1") (pin "13") (pinfunction "R1IN_13") (pintype "input"))
      (node (ref "X1") (pin "3") (pinfunction "3_3") (pintype "passive"))
    )
    (net (code "51") (name "Net-(U1-T1OUT)") (class "Default")
      (node (ref "U1") (pin "14") (pinfunction "T1OUT_14") (pintype "output"))
      (node (ref "X1") (pin "2") (pinfunction "2_2") (pintype "passive"))
    )
    (net (code "52") (name "Net-(U2-BYP)") (class "Default")
      (node (ref "C2") (pin "1") (pinfunction "1_1") (pintype "passive"))
      (node (ref "U2") (pin "2") (pinfunction "BYP_2") (pintype "bidirectional"))
    )
    (net (code "53") (name "Net-(U3-BP)") (class "Default")
      (node (ref "C18") (pin "1") (pinfunction "1_1") (pintype "passive"))
      (node (ref "U3") (pin "4") (pinfunction "BP_4") (pintype "input"))
    )
    (net (code "54") (name "VIN") (class "Default")
      (node (ref "C17") (pin "A") (pinfunction "+_A") (pintype "passive"))
      (node (ref "J1") (pin "GND") (pinfunction "GND_GND") (pintype "bidirectional"))
      (node (ref "J1") (pin "GNDBREAK") (pinfunction "GNDBREAK_GNDBREAK") (pintype "bidirectional"))
      (node (ref "J2") (pin "1") (pinfunction "1_1") (pintype "passive"))
      (node (ref "ON") (pin "3") (pinfunction "S_3") (pintype "passive"))
      (node (ref "U3") (pin "1") (pinfunction "IN_1") (pintype "input"))
    )
    (net (code "55") (name "unconnected-(IC1-CTS-Pad11)") (class "Default")
      (node (ref "IC1") (pin "11") (pinfunction "CTS_11") (pintype "input"))
    )
    (net (code "56") (name "unconnected-(IC1-DCD-Pad10)") (class "Default")
      (node (ref "IC1") (pin "10") (pinfunction "DCD_10") (pintype "input"))
    )
    (net (code "57") (name "unconnected-(IC1-DSR-Pad9)") (class "Default")
      (node (ref "IC1") (pin "9") (pinfunction "DSR_9") (pintype "input"))
    )
    (net (code "58") (name "unconnected-(IC1-DTR-Pad2)") (class "Default")
      (node (ref "IC1") (pin "2") (pinfunction "DTR_2") (pintype "output"))
    )
    (net (code "59") (name "unconnected-(IC1-OSCI-Pad27)") (class "Default")
      (node (ref "IC1") (pin "27") (pinfunction "OSCI_27") (pintype "input"))
    )
    (net (code "60") (name "unconnected-(IC1-OSCO-Pad28)") (class "Default")
      (node (ref "IC1") (pin "28") (pinfunction "OSCO_28") (pintype "output"))
    )
    (net (code "61") (name "unconnected-(IC1-PWREN-Pad14)") (class "Default")
      (node (ref "IC1") (pin "14") (pinfunction "PWREN_14") (pintype "input"))
    )
    (net (code "62") (name "unconnected-(IC1-RESET-Pad19)") (class "Default")
      (node (ref "IC1") (pin "19") (pinfunction "RESET_19") (pintype "input"))
    )
    (net (code "63") (name "unconnected-(IC1-RI-Pad6)") (class "Default")
      (node (ref "IC1") (pin "6") (pinfunction "RI_6") (pintype "input"))
    )
    (net (code "64") (name "unconnected-(IC1-RTS-Pad3)") (class "Default")
      (node (ref "IC1") (pin "3") (pinfunction "RTS_3") (pintype "output"))
    )
    (net (code "65") (name "unconnected-(IC1-SLEEP-Pad12)") (class "Default")
      (node (ref "IC1") (pin "12") (pinfunction "SLEEP_12") (pintype "input"))
    )
    (net (code "66") (name "unconnected-(IC1-TXDEN-Pad13)") (class "Default")
      (node (ref "IC1") (pin "13") (pinfunction "TXDEN_13") (pintype "input"))
    )
    (net (code "67") (name "unconnected-(J2-Pad2)") (class "Default")
      (node (ref "J2") (pin "2") (pinfunction "2_2") (pintype "passive"))
    )
    (net (code "68") (name "unconnected-(J2-Pad3)") (class "Default")
      (node (ref "J2") (pin "3") (pinfunction "3_3") (pintype "passive"))
    )
    (net (code "69") (name "unconnected-(J2-Pad4)") (class "Default")
      (node (ref "J2") (pin "4") (pinfunction "4_4") (pintype "passive"))
    )
    (net (code "70") (name "unconnected-(J2-Pad5)") (class "Default")
      (node (ref "J2") (pin "5") (pinfunction "5_5") (pintype "passive"))
    )
    (net (code "71") (name "unconnected-(JTAG-KEY-Pad7)") (class "Default")
      (node (ref "JTAG") (pin "7") (pinfunction "KEY_7") (pintype "bidirectional"))
    )
    (net (code "72") (name "unconnected-(STM32-PA0{slash}ADC123_IN0(5T)-Pad14)") (class "Default")
      (node (ref "STM32") (pin "14") (pinfunction "PA0/ADC123_IN0(5T)_14") (pintype "bidirectional"))
    )
    (net (code "73") (name "unconnected-(STM32-PA1{slash}ADC123_IN1(5T)-Pad15)") (class "Default")
      (node (ref "STM32") (pin "15") (pinfunction "PA1/ADC123_IN1(5T)_15") (pintype "bidirectional"))
    )
    (net (code "74") (name "unconnected-(STM32-PA2{slash}ADC123_IN2(5T)-Pad16)") (class "Default")
      (node (ref "STM32") (pin "16") (pinfunction "PA2/ADC123_IN2(5T)_16") (pintype "bidirectional"))
    )
    (net (code "75") (name "unconnected-(STM32-PA3{slash}ADC123_IN3(5T)-Pad17)") (class "Default")
      (node (ref "STM32") (pin "17") (pinfunction "PA3/ADC123_IN3(5T)_17") (pintype "bidirectional"))
    )
    (net (code "76") (name "unconnected-(STM32-PA4{slash}ADC12_IN4-Pad20)") (class "Default")
      (node (ref "STM32") (pin "20") (pinfunction "PA4/ADC12_IN4_20") (pintype "bidirectional"))
    )
    (net (code "77") (name "unconnected-(STM32-PA5{slash}ADC12_IN5-Pad21)") (class "Default")
      (node (ref "STM32") (pin "21") (pinfunction "PA5/ADC12_IN5_21") (pintype "bidirectional"))
    )
    (net (code "78") (name "unconnected-(STM32-PA6{slash}ADC12_IN6(5T)-Pad22)") (class "Default")
      (node (ref "STM32") (pin "22") (pinfunction "PA6/ADC12_IN6(5T)_22") (pintype "bidirectional"))
    )
    (net (code "79") (name "unconnected-(STM32-PA7{slash}TIM1_CH1N{slash}ADC12_IN7(FT)-Pad23)") (class "Default")
      (node (ref "STM32") (pin "23") (pinfunction "PA7/TIM1_CH1N/ADC12_IN7(FT)_23") (pintype "bidirectional"))
    )
    (net (code "80") (name "unconnected-(STM32-PA8{slash}TIM1_CH1(5T)-Pad41)") (class "Default")
      (node (ref "STM32") (pin "41") (pinfunction "PA8/TIM1_CH1(5T)_41") (pintype "bidirectional"))
    )
    (net (code "81") (name "unconnected-(STM32-PA11{slash}TIM1_CH4{slash}CANRX{slash}USBDM(5T)-Pad44)") (class "Default")
      (node (ref "STM32") (pin "44") (pinfunction "PA11/TIM1_CH4/CANRX/USBDM(5T)_44") (pintype "bidirectional"))
    )
    (net (code "82") (name "unconnected-(STM32-PA12{slash}CANTX{slash}USBDP(5T)-Pad45)") (class "Default")
      (node (ref "STM32") (pin "45") (pinfunction "PA12/CANTX/USBDP(5T)_45") (pintype "bidirectional"))
    )
    (net (code "83") (name "unconnected-(STM32-PB0{slash}TIM1_CH2N{slash}ADC12_IN8(5T)-Pad26)") (class "Default")
      (node (ref "STM32") (pin "26") (pinfunction "PB0/TIM1_CH2N/ADC12_IN8(5T)_26") (pintype "bidirectional"))
    )
    (net (code "84") (name "unconnected-(STM32-PB1{slash}TIM1_CH3N{slash}ADC12_IN9(5T)-Pad27)") (class "Default")
      (node (ref "STM32") (pin "27") (pinfunction "PB1/TIM1_CH3N/ADC12_IN9(5T)_27") (pintype "bidirectional"))
    )
    (net (code "85") (name "unconnected-(STM32-PB5(5T)-Pad57)") (class "Default")
      (node (ref "STM32") (pin "57") (pinfunction "PB5(5T)_57") (pintype "bidirectional"))
    )
    (net (code "86") (name "unconnected-(STM32-PB8{slash}TIM10_CH1{slash}TIM4_CH3(5T)-Pad61)") (class "Default")
      (node (ref "STM32") (pin "61") (pinfunction "PB8/TIM10_CH1/TIM4_CH3(5T)_61") (pintype "bidirectional"))
    )
    (net (code "87") (name "unconnected-(STM32-PB9{slash}TIM11_CH1{slash}TIM4_CH4(5T)-Pad62)") (class "Default")
      (node (ref "STM32") (pin "62") (pinfunction "PB9/TIM11_CH1/TIM4_CH4(5T)_62") (pintype "bidirectional"))
    )
    (net (code "88") (name "unconnected-(STM32-PB12(5T)-Pad33)") (class "Default")
      (node (ref "STM32") (pin "33") (pinfunction "PB12(5T)_33") (pintype "bidirectional"))
    )
    (net (code "89") (name "unconnected-(STM32-PB13{slash}SPI2_SCK(5T)-Pad34)") (class "Default")
      (node (ref "STM32") (pin "34") (pinfunction "PB13/SPI2_SCK(5T)_34") (pintype "bidirectional"))
    )
    (net (code "90") (name "unconnected-(STM32-PB14{slash}SPI2_MISO(5T)-Pad35)") (class "Default")
      (node (ref "STM32") (pin "35") (pinfunction "PB14/SPI2_MISO(5T)_35") (pintype "bidirectional"))
    )
    (net (code "91") (name "unconnected-(STM32-PB15{slash}SPI2_MOSI(5T)-Pad36)") (class "Default")
      (node (ref "STM32") (pin "36") (pinfunction "PB15/SPI2_MOSI(5T)_36") (pintype "bidirectional"))
    )
    (net (code "92") (name "unconnected-(STM32-PC0{slash}ADC123_IN10(5T)-Pad8)") (class "Default")
      (node (ref "STM32") (pin "8") (pinfunction "PC0/ADC123_IN10(5T)_8") (pintype "bidirectional"))
    )
    (net (code "93") (name "unconnected-(STM32-PC1{slash}ADC123_IN11(5T)-Pad9)") (class "Default")
      (node (ref "STM32") (pin "9") (pinfunction "PC1/ADC123_IN11(5T)_9") (pintype "bidirectional"))
    )
    (net (code "94") (name "unconnected-(STM32-PC2{slash}ADC123_IN12(5T)-Pad10)") (class "Default")
      (node (ref "STM32") (pin "10") (pinfunction "PC2/ADC123_IN12(5T)_10") (pintype "bidirectional"))
    )
    (net (code "95") (name "unconnected-(STM32-PC3{slash}ADC123_IN13(5T)-Pad11)") (class "Default")
      (node (ref "STM32") (pin "11") (pinfunction "PC3/ADC123_IN13(5T)_11") (pintype "bidirectional"))
    )
    (net (code "96") (name "unconnected-(STM32-PC4{slash}ADC12_IN14-Pad24)") (class "Default")
      (node (ref "STM32") (pin "24") (pinfunction "PC4/ADC12_IN14_24") (pintype "bidirectional"))
    )
    (net (code "97") (name "unconnected-(STM32-PC5{slash}ADC12_IN15-Pad25)") (class "Default")
      (node (ref "STM32") (pin "25") (pinfunction "PC5/ADC12_IN15_25") (pintype "bidirectional"))
    )
    (net (code "98") (name "unconnected-(STM32-PC8{slash}TIM3_CH3{slash}TIM8_CH3(5T)-Pad39)") (class "Default")
      (node (ref "STM32") (pin "39") (pinfunction "PC8/TIM3_CH3/TIM8_CH3(5T)_39") (pintype "bidirectional"))
    )
    (net (code "99") (name "unconnected-(STM32-PC9{slash}TIM3_CH4{slash}TIM8_CH4(5T)-Pad40)") (class "Default")
      (node (ref "STM32") (pin "40") (pinfunction "PC9/TIM3_CH4/TIM8_CH4(5T)_40") (pintype "bidirectional"))
    )
    (net (code "100") (name "unconnected-(STM32-PC10(5T)-Pad51)") (class "Default")
      (node (ref "STM32") (pin "51") (pinfunction "PC10(5T)_51") (pintype "bidirectional"))
    )
    (net (code "101") (name "unconnected-(STM32-PC11(5T)-Pad52)") (class "Default")
      (node (ref "STM32") (pin "52") (pinfunction "PC11(5T)_52") (pintype "bidirectional"))
    )
    (net (code "102") (name "unconnected-(STM32-PC12(5T)-Pad53)") (class "Default")
      (node (ref "STM32") (pin "53") (pinfunction "PC12(5T)_53") (pintype "bidirectional"))
    )
    (net (code "103") (name "unconnected-(STM32-PC13(5T)-Pad2)") (class "Default")
      (node (ref "STM32") (pin "2") (pinfunction "PC13(5T)_2") (pintype "bidirectional"))
    )
    (net (code "104") (name "unconnected-(STM32-PC15{slash}OSC32_OUT(5T)-Pad4)") (class "Default")
      (node (ref "STM32") (pin "4") (pinfunction "PC15/OSC32_OUT(5T)_4") (pintype "bidirectional"))
    )
    (net (code "105") (name "unconnected-(STM32-PD2{slash}TIM3_ETR(5T)-Pad54)") (class "Default")
      (node (ref "STM32") (pin "54") (pinfunction "PD2/TIM3_ETR(5T)_54") (pintype "bidirectional"))
    )
    (net (code "106") (name "unconnected-(STM32-VBAT-Pad1)") (class "Default")
      (node (ref "STM32") (pin "1") (pinfunction "VBAT_1") (pintype "bidirectional"))
    )
    (net (code "107") (name "unconnected-(U$1-Pad5_EXTINT0)") (class "Default")
      (node (ref "U$1") (pin "5_EXTINT0") (pinfunction "5_EXTINT0_5_EXTINT0") (pintype "bidirectional"))
    )
    (net (code "108") (name "unconnected-(U$1-Pad13_ANTON)") (class "Default")
      (node (ref "U$1") (pin "13_ANTON") (pinfunction "13_ANTON_13_ANTON") (pintype "bidirectional"))
    )
    (net (code "109") (name "unconnected-(U$1-Pad15_RESERVED)") (class "Default")
      (node (ref "U$1") (pin "15_RESERVED") (pinfunction "15_RESERVED_15_RESERVED") (pintype "bidirectional"))
    )
    (net (code "110") (name "unconnected-(U$1-Pad16_SDA2)") (class "Default")
      (node (ref "U$1") (pin "16_SDA2") (pinfunction "16_SDA2_16_SDA2") (pintype "bidirectional"))
    )
    (net (code "111") (name "unconnected-(U$1-Pad17_SCL2)") (class "Default")
      (node (ref "U$1") (pin "17_SCL2") (pinfunction "17_SCL2_17_SCL2") (pintype "bidirectional"))
    )
    (net (code "112") (name "unconnected-(U$1-Pad18_RESERVED)") (class "Default")
      (node (ref "U$1") (pin "18_RESERVED") (pinfunction "18_RESERVED_18_RESERVED") (pintype "bidirectional"))
    )
    (net (code "113") (name "unconnected-(U1-R2OUT-Pad9)") (class "Default")
      (node (ref "U1") (pin "9") (pinfunction "R2OUT_9") (pintype "output"))
    )
    (net (code "114") (name "unconnected-(U1-T2OUT-Pad7)") (class "Default")
      (node (ref "U1") (pin "7") (pinfunction "T2OUT_7") (pintype "output"))
    )
    (net (code "115") (name "unconnected-(X1-Pad1)") (class "Default")
      (node (ref "X1") (pin "1") (pinfunction "1_1") (pintype "passive"))
    )
    (net (code "116") (name "unconnected-(X1-Pad4)") (class "Default")
      (node (ref "X1") (pin "4") (pinfunction "4_4") (pintype "passive"))
    )
    (net (code "117") (name "unconnected-(X1-Pad6)") (class "Default")
      (node (ref "X1") (pin "6") (pinfunction "6_6") (pintype "passive"))
    )
    (net (code "118") (name "unconnected-(X1-Pad7)") (class "Default")
      (node (ref "X1") (pin "7") (pinfunction "7_7") (pintype "passive"))
    )
    (net (code "119") (name "unconnected-(X1-Pad8)") (class "Default")
      (node (ref "X1") (pin "8") (pinfunction "8_8") (pintype "passive"))
    )
    (net (code "120") (name "unconnected-(X1-Pad9)") (class "Default")
      (node (ref "X1") (pin "9") (pinfunction "9_9") (pintype "passive"))
    )
  )
)
